# TDS_Sensor_Unit.net
KiCad netlist of a schematic drawn in Altium Designer
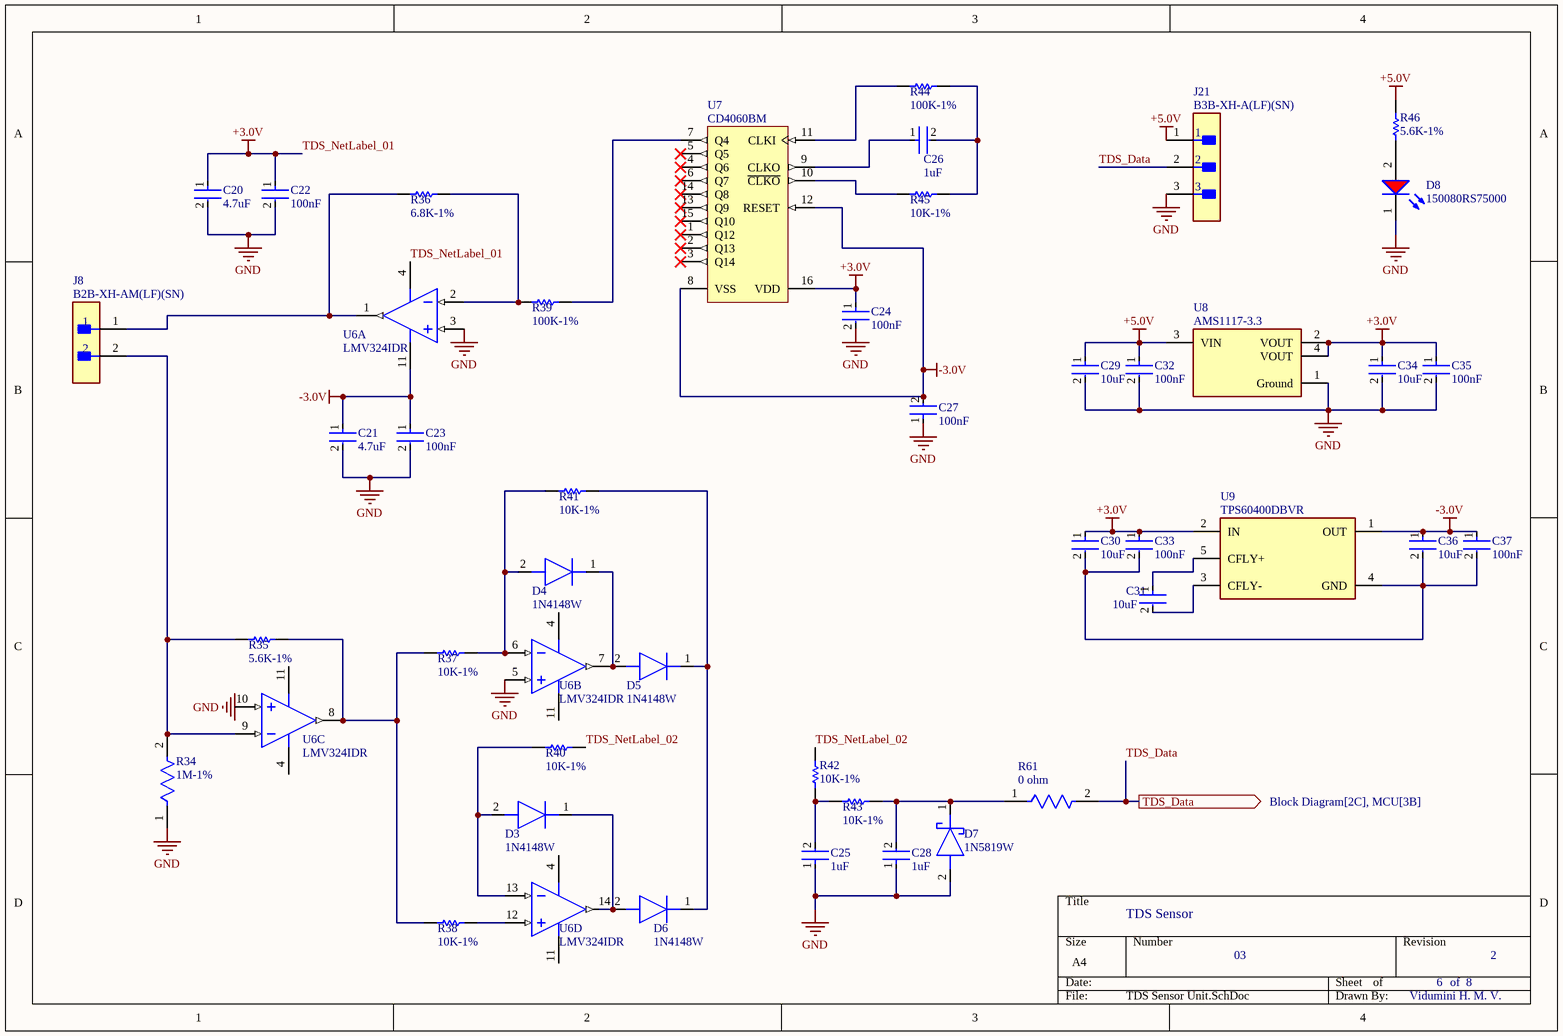
[diagram p0: TDS Sensor Unit.SchDoc]

(export (version "E")
  (design (tool "Eeschema 10.0.6"))
  (components
    (comp (ref "C20")
      (value "4.7uF")
      (footprint "FP-1206-L_3_2_0_2-W_1_6_0-MFG")
      (description "General Purpose Ceramic Capacitor, 1206, 4.7uF, 10%, X5R, 15%, 25V")
      (fields (field (name "VOLTAGE") "25V") (field (name "TOLERANCE") "10%"))
      (libsource (lib "Altium Content Vault") (part "02cd4be3c70576c341d710602a673aa"))
    )
    (comp (ref "C21")
      (value "4.7uF")
      (footprint "FP-1206-L_3_2_0_2-W_1_6_0-MFG")
      (description "General Purpose Ceramic Capacitor, 1206, 4.7uF, 10%, X5R, 15%, 25V")
      (fields (field (name "VOLTAGE") "25V") (field (name "TOLERANCE") "10%"))
      (libsource (lib "Altium Content Vault") (part "02cd4be3c70576c341d710602a673aa"))
    )
    (comp (ref "C22")
      (value "100nF")
      (footprint "FP-1206-L_3_2_0_2-W_1_6_0-IPC_C")
      (description "General Purpose Ceramic Capacitor, 1206, 100nF, 5%, X7R, 15%, 100V")
      (fields (field (name "TOLERANCE") "5%") (field (name "VOLTAGE") "100V"))
      (libsource (lib "Altium Content Vault") (part "b4654b650e69147ec39a6b967a45e02"))
    )
    (comp (ref "C23")
      (value "100nF")
      (footprint "FP-1206-L_3_2_0_2-W_1_6_0-IPC_C")
      (description "General Purpose Ceramic Capacitor, 1206, 100nF, 5%, X7R, 15%, 100V")
      (fields (field (name "TOLERANCE") "5%") (field (name "VOLTAGE") "100V"))
      (libsource (lib "Altium Content Vault") (part "b4654b650e69147ec39a6b967a45e02"))
    )
    (comp (ref "C24")
      (value "100nF")
      (footprint "FP-1206-L_3_2_0_2-W_1_6_0-IPC_C")
      (description "General Purpose Ceramic Capacitor, 1206, 100nF, 5%, X7R, 15%, 100V")
      (fields (field (name "TOLERANCE") "5%") (field (name "VOLTAGE") "100V"))
      (libsource (lib "Altium Content Vault") (part "b4654b650e69147ec39a6b967a45e02"))
    )
    (comp (ref "C25")
      (value "1uF")
      (footprint "FP-0805-L_2_01_0_2-W_1_25-MFG")
      (description "General Purpose Ceramic Capacitor, 0805, 1uF, 10%, X7R, 15%, 25V")
      (fields (field (name "TOLERANCE") "10%") (field (name "VOLTAGE") "25V"))
      (libsource (lib "Altium Content Vault") (part "b4654b650e69147ec39a6b967a45e02"))
    )
    (comp (ref "C26")
      (value "1uF")
      (footprint "FP-0805-L_2_01_0_2-W_1_25-MFG")
      (description "General Purpose Ceramic Capacitor, 0805, 1uF, 10%, X7R, 15%, 25V")
      (fields (field (name "TOLERANCE") "10%") (field (name "VOLTAGE") "25V"))
      (libsource (lib "Altium Content Vault") (part "b4654b650e69147ec39a6b967a45e02"))
    )
    (comp (ref "C27")
      (value "100nF")
      (footprint "FP-1206-L_3_2_0_2-W_1_6_0-IPC_C")
      (description "General Purpose Ceramic Capacitor, 1206, 100nF, 5%, X7R, 15%, 100V")
      (fields (field (name "TOLERANCE") "5%") (field (name "VOLTAGE") "100V"))
      (libsource (lib "Altium Content Vault") (part "b4654b650e69147ec39a6b967a45e02"))
    )
    (comp (ref "C28")
      (value "1uF")
      (footprint "FP-0805-L_2_01_0_2-W_1_25-MFG")
      (description "General Purpose Ceramic Capacitor, 0805, 1uF, 10%, X7R, 15%, 25V")
      (fields (field (name "TOLERANCE") "10%") (field (name "VOLTAGE") "25V"))
      (libsource (lib "Altium Content Vault") (part "b4654b650e69147ec39a6b967a45e02"))
    )
    (comp (ref "C29")
      (value "10uF")
      (footprint "FP-1206-L_3_2_0_2-W_1_6_0-IPC_B")
      (description "General Purpose Ceramic Capacitor, 1206, 10uF, 10%, X5R, 15%, 25V")
      (fields (field (name "TOLERANCE") "10%") (field (name "VOLTAGE") "25V"))
      (libsource (lib "Altium Content Vault") (part "02cd4be3c70576c341d710602a673aa"))
    )
    (comp (ref "C30")
      (value "10uF")
      (footprint "FP-1206-L_3_2_0_2-W_1_6_0-IPC_B")
      (description "General Purpose Ceramic Capacitor, 1206, 10uF, 10%, X5R, 15%, 25V")
      (fields (field (name "TOLERANCE") "10%") (field (name "VOLTAGE") "25V"))
      (libsource (lib "Altium Content Vault") (part "02cd4be3c70576c341d710602a673aa"))
    )
    (comp (ref "C31")
      (value "10uF")
      (footprint "FP-1206-L_3_2_0_2-W_1_6_0-IPC_B")
      (description "General Purpose Ceramic Capacitor, 1206, 10uF, 10%, X5R, 15%, 25V")
      (fields (field (name "TOLERANCE") "10%") (field (name "VOLTAGE") "25V"))
      (libsource (lib "Altium Content Vault") (part "02cd4be3c70576c341d710602a673aa"))
    )
    (comp (ref "C32")
      (value "100nF")
      (footprint "FP-1206-L_3_2_0_2-W_1_6_0-IPC_C")
      (description "General Purpose Ceramic Capacitor, 1206, 100nF, 5%, X7R, 15%, 100V")
      (fields (field (name "TOLERANCE") "5%") (field (name "VOLTAGE") "100V"))
      (libsource (lib "Altium Content Vault") (part "b4654b650e69147ec39a6b967a45e02"))
    )
    (comp (ref "C33")
      (value "100nF")
      (footprint "FP-1206-L_3_2_0_2-W_1_6_0-IPC_C")
      (description "General Purpose Ceramic Capacitor, 1206, 100nF, 5%, X7R, 15%, 100V")
      (fields (field (name "TOLERANCE") "5%") (field (name "VOLTAGE") "100V"))
      (libsource (lib "Altium Content Vault") (part "b4654b650e69147ec39a6b967a45e02"))
    )
    (comp (ref "C34")
      (value "10uF")
      (footprint "FP-1206-L_3_2_0_2-W_1_6_0-IPC_B")
      (description "General Purpose Ceramic Capacitor, 1206, 10uF, 10%, X5R, 15%, 25V")
      (fields (field (name "TOLERANCE") "10%") (field (name "VOLTAGE") "25V"))
      (libsource (lib "Altium Content Vault") (part "02cd4be3c70576c341d710602a673aa"))
    )
    (comp (ref "C35")
      (value "100nF")
      (footprint "FP-1206-L_3_2_0_2-W_1_6_0-IPC_C")
      (description "General Purpose Ceramic Capacitor, 1206, 100nF, 5%, X7R, 15%, 100V")
      (fields (field (name "TOLERANCE") "5%") (field (name "VOLTAGE") "100V"))
      (libsource (lib "Altium Content Vault") (part "b4654b650e69147ec39a6b967a45e02"))
    )
    (comp (ref "C36")
      (value "10uF")
      (footprint "FP-1206-L_3_2_0_2-W_1_6_0-IPC_B")
      (description "General Purpose Ceramic Capacitor, 1206, 10uF, 10%, X5R, 15%, 25V")
      (fields (field (name "TOLERANCE") "10%") (field (name "VOLTAGE") "25V"))
      (libsource (lib "Altium Content Vault") (part "02cd4be3c70576c341d710602a673aa"))
    )
    (comp (ref "C37")
      (value "100nF")
      (footprint "FP-1206-L_3_2_0_2-W_1_6_0-IPC_C")
      (description "General Purpose Ceramic Capacitor, 1206, 100nF, 5%, X7R, 15%, 100V")
      (fields (field (name "TOLERANCE") "5%") (field (name "VOLTAGE") "100V"))
      (libsource (lib "Altium Content Vault") (part "b4654b650e69147ec39a6b967a45e02"))
    )
    (comp (ref "D3")
      (value "1N4148W")
      (footprint "SamacSys:SOD3716X125N")
      (description "Diode")
      (fields (field (name "MOUSER PART NUMBER") "583-1N4148W"))
      (libsource (lib "*") (part "1N4148W"))
    )
    (comp (ref "D4")
      (value "1N4148W")
      (footprint "SamacSys:SOD3716X125N")
      (description "Diode")
      (fields (field (name "MOUSER PART NUMBER") "583-1N4148W"))
      (libsource (lib "*") (part "1N4148W"))
    )
    (comp (ref "D5")
      (value "1N4148W")
      (footprint "SamacSys:SOD3716X125N")
      (description "Diode")
      (fields (field (name "MOUSER PART NUMBER") "583-1N4148W"))
      (libsource (lib "*") (part "1N4148W"))
    )
    (comp (ref "D6")
      (value "1N4148W")
      (footprint "SamacSys:SOD3716X125N")
      (description "Diode")
      (fields (field (name "MOUSER PART NUMBER") "583-1N4148W"))
      (libsource (lib "*") (part "1N4148W"))
    )
    (comp (ref "D7")
      (value "1N5819W")
      (footprint "SamacSys:SODFL3618X110N")
      (description "Schottky Diode")
      (libsource (lib "*") (part "1N5819W"))
    )
    (comp (ref "D8")
      (value "150080RS75000")
      (footprint "WL-SMCW_0805_150080xx75000")
      (libsource (lib "Altium Content Vault") (part "LED_Red_2A-1K"))
    )
    (comp (ref "J8")
      (value "B2B-XH-AM(LF)(SN)")
      (footprint "FP-B2B-XH-AM_LF_SN-MFG")
      (description "CONN HEADER VERT 2POS 2.5MM")
      (libsource (lib "Altium Content Vault") (part "3bc925449376181038e59eaffc5286c"))
    )
    (comp (ref "J21")
      (value "B3B-XH-A(LF)(SN)")
      (footprint "FP-B3B-XH-A_LF_SN-MFG")
      (description "CONN HEADER VERT 3POS 2.5MM")
      (libsource (lib "Altium Content Vault") (part "0d3f023dd272f625e17a2be33dea85f"))
    )
    (comp (ref "R34")
      (value "1M-1%")
      (footprint "FP-CRCW1206-e3-MFG")
      (description "RES Thick Film, 1MΩ, 1%, 0.25W, 100ppm/°C, 1206")
      (fields (field (name "TOLERANCE") "1%"))
      (libsource (lib "Altium Content Vault") (part "1029c3af85768c4190bb7ad29bc67b5"))
    )
    (comp (ref "R35")
      (value "5.6K-1%")
      (footprint "RESC3116X65X40ML10T20")
      (description "Chip Resistor, 10 KOhm, +/- 1%, 0.25 W, -55 to 155 degC, 1206 (3216 Metric), RoHS, Tape and Reel")
      (fields (field (name "TOLERANCE") "1%") (field (name "MANUFACTURER") "Yageo"))
      (libsource (lib "Altium Content Vault") (part "RES-2"))
    )
    (comp (ref "R36")
      (value "6.8K-1%")
      (footprint "RESC3116X65X40ML10T20")
      (description "Chip Resistor, 10 KOhm, +/- 1%, 0.25 W, -55 to 155 degC, 1206 (3216 Metric), RoHS, Tape and Reel")
      (fields (field (name "TOLERANCE") "1%") (field (name "MANUFACTURER") "Yageo"))
      (libsource (lib "Altium Content Vault") (part "RES-2"))
    )
    (comp (ref "R37")
      (value "10K-1%")
      (footprint "RESC3116X65X40ML10T20")
      (description "Chip Resistor, 10 KOhm, +/- 1%, 0.25 W, -55 to 155 degC, 1206 (3216 Metric), RoHS, Tape and Reel")
      (fields (field (name "TOLERANCE") "1%") (field (name "MANUFACTURER") "Yageo"))
      (libsource (lib "Altium Content Vault") (part "RES-2"))
    )
    (comp (ref "R38")
      (value "10K-1%")
      (footprint "RESC3116X65X40ML10T20")
      (description "Chip Resistor, 10 KOhm, +/- 1%, 0.25 W, -55 to 155 degC, 1206 (3216 Metric), RoHS, Tape and Reel")
      (fields (field (name "TOLERANCE") "1%") (field (name "MANUFACTURER") "Yageo"))
      (libsource (lib "Altium Content Vault") (part "RES-2"))
    )
    (comp (ref "R39")
      (value "100K-1%")
      (footprint "RESC3116X65X40ML10T20")
      (description "Chip Resistor, 100 KOhm, +/- 1%, 0.25 W, -55 to 155 degC, 1206 (3216 Metric), RoHS, Tape and Reel")
      (fields (field (name "TOLERANCE") "1%") (field (name "MANUFACTURER") "Yageo"))
      (libsource (lib "Altium Content Vault") (part "RES-2"))
    )
    (comp (ref "R40")
      (value "10K-1%")
      (footprint "RESC3116X65X40ML10T20")
      (description "Chip Resistor, 10 KOhm, +/- 1%, 0.25 W, -55 to 155 degC, 1206 (3216 Metric), RoHS, Tape and Reel")
      (fields (field (name "TOLERANCE") "1%") (field (name "MANUFACTURER") "Yageo"))
      (libsource (lib "Altium Content Vault") (part "RES-2"))
    )
    (comp (ref "R41")
      (value "10K-1%")
      (footprint "RESC3116X65X40ML10T20")
      (description "Chip Resistor, 10 KOhm, +/- 1%, 0.25 W, -55 to 155 degC, 1206 (3216 Metric), RoHS, Tape and Reel")
      (fields (field (name "TOLERANCE") "1%") (field (name "MANUFACTURER") "Yageo"))
      (libsource (lib "Altium Content Vault") (part "RES-2"))
    )
    (comp (ref "R42")
      (value "10K-1%")
      (footprint "RESC3116X65X40ML10T20")
      (description "Chip Resistor, 10 KOhm, +/- 1%, 0.25 W, -55 to 155 degC, 1206 (3216 Metric), RoHS, Tape and Reel")
      (fields (field (name "TOLERANCE") "1%") (field (name "MANUFACTURER") "Yageo"))
      (libsource (lib "Altium Content Vault") (part "RES-2"))
    )
    (comp (ref "R43")
      (value "10K-1%")
      (footprint "RESC3116X65X40ML10T20")
      (description "Chip Resistor, 10 KOhm, +/- 1%, 0.25 W, -55 to 155 degC, 1206 (3216 Metric), RoHS, Tape and Reel")
      (fields (field (name "TOLERANCE") "1%") (field (name "MANUFACTURER") "Yageo"))
      (libsource (lib "Altium Content Vault") (part "RES-2"))
    )
    (comp (ref "R44")
      (value "100K-1%")
      (footprint "RESC3116X65X40ML10T20")
      (description "Chip Resistor, 100 KOhm, +/- 1%, 0.25 W, -55 to 155 degC, 1206 (3216 Metric), RoHS, Tape and Reel")
      (fields (field (name "TOLERANCE") "1%") (field (name "MANUFACTURER") "Yageo"))
      (libsource (lib "Altium Content Vault") (part "RES-2"))
    )
    (comp (ref "R45")
      (value "10K-1%")
      (footprint "RESC3116X65X40ML10T20")
      (description "Chip Resistor, 10 KOhm, +/- 1%, 0.25 W, -55 to 155 degC, 1206 (3216 Metric), RoHS, Tape and Reel")
      (fields (field (name "TOLERANCE") "1%") (field (name "MANUFACTURER") "Yageo"))
      (libsource (lib "Altium Content Vault") (part "RES-2"))
    )
    (comp (ref "R46")
      (value "5.6K-1%")
      (footprint "RESC3116X65X40ML10T20")
      (description "Chip Resistor, 10 KOhm, +/- 1%, 0.25 W, -55 to 155 degC, 1206 (3216 Metric), RoHS, Tape and Reel")
      (fields (field (name "TOLERANCE") "1%") (field (name "MANUFACTURER") "Yageo"))
      (libsource (lib "Altium Content Vault") (part "RES-2"))
    )
    (comp (ref "R61")
      (value "0 ohm")
      (footprint "FP-AF0603-IPC_B")
      (description "Anti-Sulfurated Chip Resistors Automotive Grade 1.5kΩ 1% 100ppm/°C 0603")
      (fields (field (name "TOLERANCE") "1%"))
      (libsource (lib "Altium Content Vault") (part "1029c3af85768c4190bb7ad29bc67b5"))
    )
    (comp (ref "U6")
      (value "LMV324IDR")
      (footprint "D0014A_V")
      (libsource (lib "Altium Content Vault") (part "TI-LMV324-D-14"))
    )
    (comp (ref "U7")
      (value "CD4060BM")
      (footprint "D0016A_M")
      (fields (field (name "MANUFACTURER") "Texas Instruments"))
      (libsource (lib "Altium Content Vault") (part "TI-CD4060B-16"))
    )
    (comp (ref "U8")
      (value "AMS1117-3.3")
      (footprint "FP-AMS1117-IPC_C")
      (description "LDO Voltage Regulators 1A, 3.3V")
      (fields
        (field (name "OCTOPART") "https://octopart.com/ams1117-3.3-advanced+monolithic+systems-25899300")
        (field (name "MANUFACTURER") "Advanced Monolithic Systems")
      )
      (libsource (lib "Altium Content Vault") (part "8bdbb5f8e77002000e30dd2845d0354"))
    )
    (comp (ref "U9")
      (value "TPS60400DBVR")
      (footprint "FP-DBV0005A-IPC_B")
      (description "IC REG CHARG PUMP INV 60MA SOT23")
      (libsource (lib "Altium Content Vault") (part "027376aeb0d6df1338393bd3c828556"))
    )
  )
  (nets
    (net (code "1") (name "+3.0V") (class "Default")
      (node (ref "C20") (pin "1") (pinfunction "1_1") (pintype "passive"))
      (node (ref "C22") (pin "1") (pinfunction "1_1") (pintype "passive"))
      (node (ref "C24") (pin "1") (pinfunction "1_1") (pintype "passive"))
      (node (ref "C30") (pin "1") (pinfunction "1_1") (pintype "passive"))
      (node (ref "C33") (pin "1") (pinfunction "1_1") (pintype "passive"))
      (node (ref "C34") (pin "1") (pinfunction "1_1") (pintype "passive"))
      (node (ref "C35") (pin "1") (pinfunction "1_1") (pintype "passive"))
      (node (ref "U6") (pin "4") (pinfunction "VCC+_4") (pintype "power_in"))
      (node (ref "U7") (pin "16") (pinfunction "VDD_16") (pintype "power_in"))
      (node (ref "U8") (pin "2") (pinfunction "VOUT_2") (pintype "passive"))
      (node (ref "U8") (pin "4") (pinfunction "VOUT_4") (pintype "passive"))
      (node (ref "U9") (pin "2") (pinfunction "IN_2") (pintype "power_in"))
    )
    (net (code "2") (name "+5.0V") (class "Default")
      (node (ref "C29") (pin "1") (pinfunction "1_1") (pintype "passive"))
      (node (ref "C32") (pin "1") (pinfunction "1_1") (pintype "passive"))
      (node (ref "J21") (pin "1") (pinfunction "1_1") (pintype "passive"))
      (node (ref "R46") (pin "2") (pinfunction "2_2") (pintype "passive"))
      (node (ref "U8") (pin "3") (pinfunction "VIN_3") (pintype "power_in"))
    )
    (net (code "3") (name "-3.0V") (class "Default")
      (node (ref "C21") (pin "1") (pinfunction "1_1") (pintype "passive"))
      (node (ref "C23") (pin "1") (pinfunction "1_1") (pintype "passive"))
      (node (ref "C27") (pin "2") (pinfunction "2_2") (pintype "passive"))
      (node (ref "C36") (pin "1") (pinfunction "1_1") (pintype "passive"))
      (node (ref "C37") (pin "1") (pinfunction "1_1") (pintype "passive"))
      (node (ref "U6") (pin "11") (pinfunction "GND_11") (pintype "power_in"))
      (node (ref "U7") (pin "12") (pinfunction "RESET_12") (pintype "input"))
      (node (ref "U7") (pin "8") (pinfunction "VSS_8") (pintype "power_in"))
      (node (ref "U9") (pin "1") (pinfunction "OUT_1") (pintype "power_in"))
    )
    (net (code "4") (name "/TDS_Data") (class "Default")
      (node (ref "J21") (pin "2") (pinfunction "2_2") (pintype "passive"))
      (node (ref "R61") (pin "2") (pinfunction "2_2") (pintype "passive"))
    )
    (net (code "5") (name "/TDS_NetLabel_02") (class "Default")
      (node (ref "R40") (pin "2") (pinfunction "2_2") (pintype "passive"))
      (node (ref "R42") (pin "1") (pinfunction "1_1") (pintype "passive"))
    )
    (net (code "6") (name "GND") (class "Default")
      (node (ref "C20") (pin "2") (pinfunction "2_2") (pintype "passive"))
      (node (ref "C21") (pin "2") (pinfunction "2_2") (pintype "passive"))
      (node (ref "C22") (pin "2") (pinfunction "2_2") (pintype "passive"))
      (node (ref "C23") (pin "2") (pinfunction "2_2") (pintype "passive"))
      (node (ref "C24") (pin "2") (pinfunction "2_2") (pintype "passive"))
      (node (ref "C25") (pin "1") (pinfunction "1_1") (pintype "passive"))
      (node (ref "C27") (pin "1") (pinfunction "1_1") (pintype "passive"))
      (node (ref "C28") (pin "1") (pinfunction "1_1") (pintype "passive"))
      (node (ref "C29") (pin "2") (pinfunction "2_2") (pintype "passive"))
      (node (ref "C32") (pin "2") (pinfunction "2_2") (pintype "passive"))
      (node (ref "C34") (pin "2") (pinfunction "2_2") (pintype "passive"))
      (node (ref "C35") (pin "2") (pinfunction "2_2") (pintype "passive"))
      (node (ref "D7") (pin "2") (pinfunction "A_2") (pintype "passive"))
      (node (ref "D8") (pin "1") (pinfunction "K_1") (pintype "passive"))
      (node (ref "J21") (pin "3") (pinfunction "3_3") (pintype "passive"))
      (node (ref "R34") (pin "1") (pinfunction "1_1") (pintype "passive"))
      (node (ref "U6") (pin "3") (pinfunction "1IN+_3") (pintype "input"))
      (node (ref "U6") (pin "5") (pinfunction "2IN+_5") (pintype "input"))
      (node (ref "U8") (pin "1") (pinfunction "Ground_1") (pintype "power_in"))
    )
    (net (code "7") (name "Net-(C25-Pad2)") (class "Default")
      (node (ref "C25") (pin "2") (pinfunction "2_2") (pintype "passive"))
      (node (ref "R42") (pin "2") (pinfunction "2_2") (pintype "passive"))
      (node (ref "R43") (pin "1") (pinfunction "1_1") (pintype "passive"))
    )
    (net (code "8") (name "Net-(C26-Pad2)") (class "Default")
      (node (ref "C26") (pin "2") (pinfunction "2_2") (pintype "passive"))
      (node (ref "R44") (pin "2") (pinfunction "2_2") (pintype "passive"))
      (node (ref "R45") (pin "2") (pinfunction "2_2") (pintype "passive"))
    )
    (net (code "9") (name "Net-(D3-A)") (class "Default")
      (node (ref "D3") (pin "2") (pinfunction "A_2") (pintype "passive"))
      (node (ref "R40") (pin "1") (pinfunction "1_1") (pintype "passive"))
      (node (ref "U6") (pin "13") (pinfunction "4IN-_13") (pintype "input"))
    )
    (net (code "10") (name "Net-(D3-K)") (class "Default")
      (node (ref "D3") (pin "1") (pinfunction "K_1") (pintype "passive"))
      (node (ref "D6") (pin "2") (pinfunction "A_2") (pintype "passive"))
      (node (ref "U6") (pin "14") (pinfunction "4OUT_14") (pintype "output"))
    )
    (net (code "11") (name "Net-(D4-A)") (class "Default")
      (node (ref "D4") (pin "2") (pinfunction "A_2") (pintype "passive"))
      (node (ref "R37") (pin "2") (pinfunction "2_2") (pintype "passive"))
      (node (ref "R41") (pin "1") (pinfunction "1_1") (pintype "passive"))
      (node (ref "U6") (pin "6") (pinfunction "2IN-_6") (pintype "input"))
    )
    (net (code "12") (name "Net-(D4-K)") (class "Default")
      (node (ref "D4") (pin "1") (pinfunction "K_1") (pintype "passive"))
      (node (ref "D5") (pin "2") (pinfunction "A_2") (pintype "passive"))
      (node (ref "U6") (pin "7") (pinfunction "2OUT_7") (pintype "output"))
    )
    (net (code "13") (name "Net-(D5-K)") (class "Default")
      (node (ref "D5") (pin "1") (pinfunction "K_1") (pintype "passive"))
      (node (ref "D6") (pin "1") (pinfunction "K_1") (pintype "passive"))
      (node (ref "R41") (pin "2") (pinfunction "2_2") (pintype "passive"))
    )
    (net (code "14") (name "Net-(D7-K)") (class "Default")
      (node (ref "C28") (pin "2") (pinfunction "2_2") (pintype "passive"))
      (node (ref "D7") (pin "1") (pinfunction "K_1") (pintype "passive"))
      (node (ref "R43") (pin "2") (pinfunction "2_2") (pintype "passive"))
      (node (ref "R61") (pin "1") (pinfunction "1_1") (pintype "passive"))
    )
    (net (code "15") (name "Net-(D8-A)") (class "Default")
      (node (ref "D8") (pin "2") (pinfunction "A_2") (pintype "passive"))
      (node (ref "R46") (pin "1") (pinfunction "1_1") (pintype "passive"))
    )
    (net (code "16") (name "Net-(U6A-1IN-)") (class "Default")
      (node (ref "R36") (pin "2") (pinfunction "2_2") (pintype "passive"))
      (node (ref "R39") (pin "1") (pinfunction "1_1") (pintype "passive"))
      (node (ref "U6") (pin "2") (pinfunction "1IN-_2") (pintype "input"))
    )
    (net (code "17") (name "Net-(U6A-1OUT)") (class "Default")
      (node (ref "J8") (pin "1") (pinfunction "1_1") (pintype "passive"))
      (node (ref "R36") (pin "1") (pinfunction "1_1") (pintype "passive"))
      (node (ref "U6") (pin "1") (pinfunction "1OUT_1") (pintype "output"))
    )
    (net (code "18") (name "Net-(U6C-3IN-)") (class "Default")
      (node (ref "J8") (pin "2") (pinfunction "2_2") (pintype "passive"))
      (node (ref "R34") (pin "2") (pinfunction "2_2") (pintype "passive"))
      (node (ref "R35") (pin "1") (pinfunction "1_1") (pintype "passive"))
      (node (ref "U6") (pin "9") (pinfunction "3IN-_9") (pintype "input"))
    )
    (net (code "19") (name "Net-(U6C-3OUT)") (class "Default")
      (node (ref "R35") (pin "2") (pinfunction "2_2") (pintype "passive"))
      (node (ref "R37") (pin "1") (pinfunction "1_1") (pintype "passive"))
      (node (ref "R38") (pin "1") (pinfunction "1_1") (pintype "passive"))
      (node (ref "U6") (pin "8") (pinfunction "3OUT_8") (pintype "output"))
    )
    (net (code "20") (name "Net-(U6D-4IN+)") (class "Default")
      (node (ref "R38") (pin "2") (pinfunction "2_2") (pintype "passive"))
      (node (ref "U6") (pin "12") (pinfunction "4IN+_12") (pintype "input"))
    )
    (net (code "21") (name "Net-(U7-CLKI)") (class "Default")
      (node (ref "R44") (pin "1") (pinfunction "1_1") (pintype "passive"))
      (node (ref "U7") (pin "11") (pinfunction "CLKI_11") (pintype "input"))
    )
    (net (code "22") (name "Net-(U7-CLKO)") (class "Default")
      (node (ref "C26") (pin "1") (pinfunction "1_1") (pintype "passive"))
      (node (ref "U7") (pin "9") (pinfunction "CLKO_9") (pintype "output"))
    )
    (net (code "23") (name "Net-(U7-Q4)") (class "Default")
      (node (ref "R39") (pin "2") (pinfunction "2_2") (pintype "passive"))
      (node (ref "U7") (pin "7") (pinfunction "Q4_7") (pintype "output"))
    )
    (net (code "24") (name "Net-(U7-~{CLKO})") (class "Default")
      (node (ref "R45") (pin "1") (pinfunction "1_1") (pintype "passive"))
      (node (ref "U7") (pin "10") (pinfunction "~{CLKO}_10") (pintype "output"))
    )
    (net (code "25") (name "Net-(U9-CFLY+)") (class "Default")
      (node (ref "C31") (pin "1") (pinfunction "1_1") (pintype "passive"))
      (node (ref "U9") (pin "5") (pinfunction "CFLY+_5") (pintype "passive"))
    )
    (net (code "26") (name "Net-(U9-CFLY-)") (class "Default")
      (node (ref "C31") (pin "2") (pinfunction "2_2") (pintype "passive"))
      (node (ref "U9") (pin "3") (pinfunction "CFLY-_3") (pintype "passive"))
    )
    (net (code "27") (name "Net-(U9-GND)") (class "Default")
      (node (ref "C30") (pin "2") (pinfunction "2_2") (pintype "passive"))
      (node (ref "C33") (pin "2") (pinfunction "2_2") (pintype "passive"))
      (node (ref "C36") (pin "2") (pinfunction "2_2") (pintype "passive"))
      (node (ref "C37") (pin "2") (pinfunction "2_2") (pintype "passive"))
      (node (ref "U9") (pin "4") (pinfunction "GND_4") (pintype "power_in"))
    )
    (net (code "28") (name "unconnected-(U6B-GND-Pad11)") (class "Default")
      (node (ref "U6") (pin "11") (pinfunction "GND_11") (pintype "power_in"))
    )
    (net (code "29") (name "unconnected-(U6B-VCC+-Pad4)") (class "Default")
      (node (ref "U6") (pin "4") (pinfunction "VCC+_4") (pintype "power_in"))
    )
    (net (code "30") (name "unconnected-(U6C-3IN+-Pad10)") (class "Default")
      (node (ref "U6") (pin "10") (pinfunction "3IN+_10") (pintype "input"))
    )
    (net (code "31") (name "unconnected-(U6C-GND-Pad11)") (class "Default")
      (node (ref "U6") (pin "11") (pinfunction "GND_11") (pintype "power_in"))
    )
    (net (code "32") (name "unconnected-(U6C-VCC+-Pad4)") (class "Default")
      (node (ref "U6") (pin "4") (pinfunction "VCC+_4") (pintype "power_in"))
    )
    (net (code "33") (name "unconnected-(U6D-GND-Pad11)") (class "Default")
      (node (ref "U6") (pin "11") (pinfunction "GND_11") (pintype "power_in"))
    )
    (net (code "34") (name "unconnected-(U6D-VCC+-Pad4)") (class "Default")
      (node (ref "U6") (pin "4") (pinfunction "VCC+_4") (pintype "power_in"))
    )
    (net (code "35") (name "unconnected-(U7-Q5-Pad5)") (class "Default")
      (node (ref "U7") (pin "5") (pinfunction "Q5_5") (pintype "output+no_connect"))
    )
    (net (code "36") (name "unconnected-(U7-Q6-Pad4)") (class "Default")
      (node (ref "U7") (pin "4") (pinfunction "Q6_4") (pintype "output+no_connect"))
    )
    (net (code "37") (name "unconnected-(U7-Q7-Pad6)") (class "Default")
      (node (ref "U7") (pin "6") (pinfunction "Q7_6") (pintype "output+no_connect"))
    )
    (net (code "38") (name "unconnected-(U7-Q8-Pad14)") (class "Default")
      (node (ref "U7") (pin "14") (pinfunction "Q8_14") (pintype "output+no_connect"))
    )
    (net (code "39") (name "unconnected-(U7-Q9-Pad13)") (class "Default")
      (node (ref "U7") (pin "13") (pinfunction "Q9_13") (pintype "output+no_connect"))
    )
    (net (code "40") (name "unconnected-(U7-Q10-Pad15)") (class "Default")
      (node (ref "U7") (pin "15") (pinfunction "Q10_15") (pintype "output+no_connect"))
    )
    (net (code "41") (name "unconnected-(U7-Q12-Pad1)") (class "Default")
      (node (ref "U7") (pin "1") (pinfunction "Q12_1") (pintype "output+no_connect"))
    )
    (net (code "42") (name "unconnected-(U7-Q13-Pad2)") (class "Default")
      (node (ref "U7") (pin "2") (pinfunction "Q13_2") (pintype "output+no_connect"))
    )
    (net (code "43") (name "unconnected-(U7-Q14-Pad3)") (class "Default")
      (node (ref "U7") (pin "3") (pinfunction "Q14_3") (pintype "output+no_connect"))
    )
  )
)
